# avr-atmega328p-pth.net
KiCad netlist of a schematic drawn in EAGLE
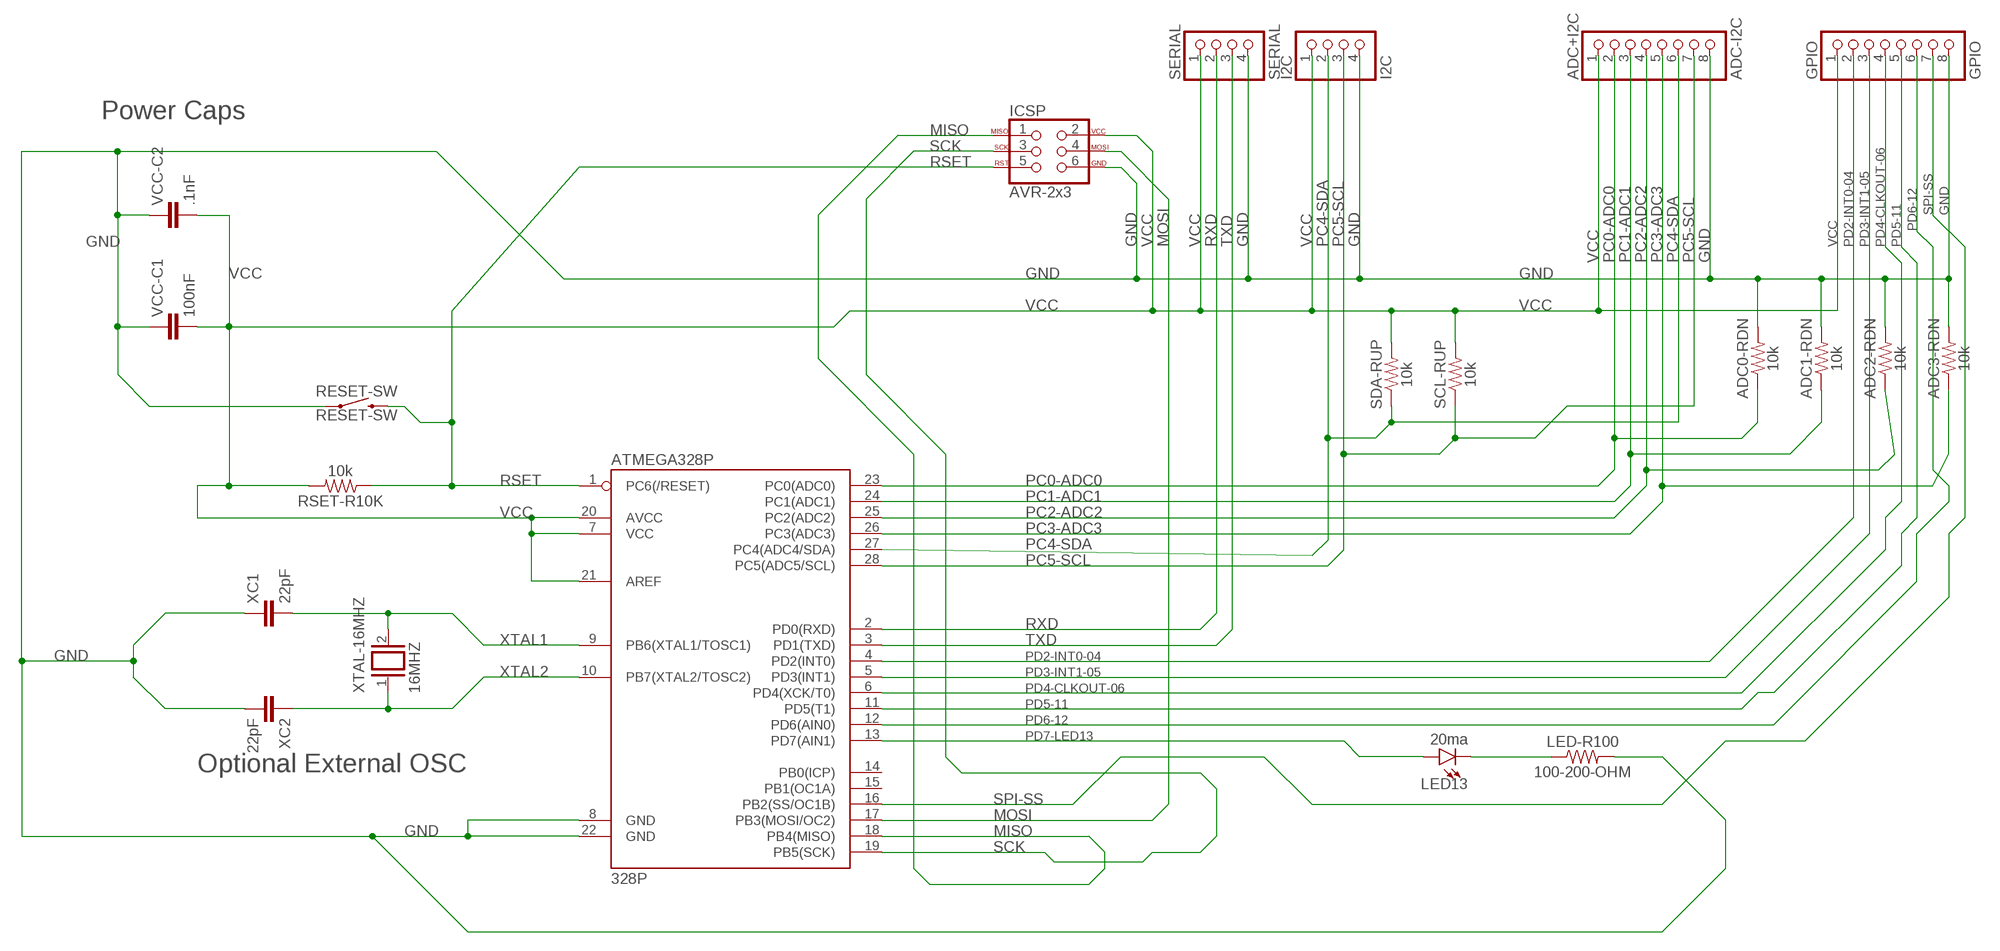
[diagram p0: schematic, sheet 1]

(export (version "E")
  (design (tool "Eeschema 10.0.6"))
  (components
    (comp (ref "ADC+I2C")
      (value "ADC-I2C")
      (footprint "eagle-import:1X08")
      (libsource (lib "eagle-import") (part "PINHD-1X8"))
    )
    (comp (ref "ADC0-RDN")
      (value "10k")
      (footprint "eagle-import:AXIAL-0.3")
      (libsource (lib "eagle-import") (part "10KOHM-HORIZ-1/4W-5%"))
    )
    (comp (ref "ADC1-RDN")
      (value "10k")
      (footprint "eagle-import:AXIAL-0.3")
      (libsource (lib "eagle-import") (part "10KOHM-HORIZ-1/4W-5%"))
    )
    (comp (ref "ADC2-RDN")
      (value "10k")
      (footprint "eagle-import:AXIAL-0.3")
      (libsource (lib "eagle-import") (part "10KOHM-HORIZ-1/4W-5%"))
    )
    (comp (ref "ADC3-RDN")
      (value "10k")
      (footprint "eagle-import:AXIAL-0.3")
      (libsource (lib "eagle-import") (part "10KOHM-HORIZ-1/4W-5%"))
    )
    (comp (ref "ATMEGA328P")
      (value "328P")
      (footprint "eagle-import:DIP28")
      (libsource (lib "eagle-import") (part "ATMEGA328P_PDIP"))
    )
    (comp (ref "GPIO")
      (value "GPIO")
      (footprint "eagle-import:1X08")
      (libsource (lib "eagle-import") (part "PINHD-1X8"))
    )
    (comp (ref "I2C")
      (value "I2C")
      (footprint "eagle-import:1X04")
      (libsource (lib "eagle-import") (part "PINHD-1X4"))
    )
    (comp (ref "ICSP")
      (value "AVR-2x3")
      (footprint "eagle-import:2X3_LOCK")
      (libsource (lib "eagle-import") (part "AVR_SPI_PROG_3X22X3_LOCK"))
    )
    (comp (ref "LED-R100")
      (value "100-200-OHM")
      (footprint "eagle-import:AXIAL-0.3")
      (libsource (lib "eagle-import") (part "10KOHM-HORIZ-1/4W-5%"))
    )
    (comp (ref "LED13")
      (value "20ma")
      (footprint "eagle-import:LED_3MM")
      (libsource (lib "eagle-import") (part "LED3MM"))
    )
    (comp (ref "RESET-SW")
      (value "RESET-SW")
      (footprint "eagle-import:TACTILE_SWITCH_PTH_6.0MM")
      (libsource (lib "eagle-import") (part "MOMENTARY-SWITCH-SPST-PTH-6.0MM"))
    )
    (comp (ref "RSET-R10K")
      (value "10k")
      (footprint "eagle-import:AXIAL-0.3")
      (libsource (lib "eagle-import") (part "10KOHM-HORIZ-1/4W-5%"))
    )
    (comp (ref "SCL-RUP")
      (value "10k")
      (footprint "eagle-import:AXIAL-0.3")
      (libsource (lib "eagle-import") (part "10KOHM-HORIZ-1/4W-5%"))
    )
    (comp (ref "SDA-RUP")
      (value "10k")
      (footprint "eagle-import:AXIAL-0.3")
      (libsource (lib "eagle-import") (part "10KOHM-HORIZ-1/4W-5%"))
    )
    (comp (ref "SERIAL")
      (value "SERIAL")
      (footprint "eagle-import:1X04")
      (libsource (lib "eagle-import") (part "PINHD-1X4"))
    )
    (comp (ref "VCC-C1")
      (value "100nF")
      (footprint "eagle-import:CAP-PTH-2.54")
      (libsource (lib "eagle-import") (part "22PF-PTH-2.54MM-200V-5%"))
    )
    (comp (ref "VCC-C2")
      (value ".1nF")
      (footprint "eagle-import:CAP-PTH-2.54")
      (libsource (lib "eagle-import") (part "22PF-PTH-2.54MM-200V-5%"))
    )
    (comp (ref "XC1")
      (value "22pF")
      (footprint "eagle-import:CAP-PTH-2.54")
      (libsource (lib "eagle-import") (part "22PF-PTH-2.54MM-200V-5%"))
    )
    (comp (ref "XC2")
      (value "22pF")
      (footprint "eagle-import:CAP-PTH-2.54")
      (libsource (lib "eagle-import") (part "22PF-PTH-2.54MM-200V-5%"))
    )
    (comp (ref "XTAL-16MHZ")
      (value "16MHZ")
      (footprint "eagle-import:QS")
      (libsource (lib "eagle-import") (part "XTAL/S"))
    )
  )
  (nets
    (net (code "1") (name "/GND") (class "Default")
      (node (ref "ADC+I2C") (pin "8") (pinfunction "8_8") (pintype "passive"))
      (node (ref "ADC0-RDN") (pin "P$2") (pinfunction "2_P$2") (pintype "passive"))
      (node (ref "ADC1-RDN") (pin "P$2") (pinfunction "2_P$2") (pintype "passive"))
      (node (ref "ADC2-RDN") (pin "P$2") (pinfunction "2_P$2") (pintype "passive"))
      (node (ref "ADC3-RDN") (pin "P$2") (pinfunction "2_P$2") (pintype "passive"))
      (node (ref "ATMEGA328P") (pin "22") (pinfunction "GND_22") (pintype "bidirectional"))
      (node (ref "ATMEGA328P") (pin "8") (pinfunction "GND_8") (pintype "bidirectional"))
      (node (ref "GPIO") (pin "8") (pinfunction "8_8") (pintype "passive"))
      (node (ref "I2C") (pin "4") (pinfunction "4_4") (pintype "passive"))
      (node (ref "ICSP") (pin "6") (pinfunction "6_6") (pintype "passive"))
      (node (ref "LED-R100") (pin "P$2") (pinfunction "2_P$2") (pintype "passive"))
      (node (ref "RESET-SW") (pin "1") (pinfunction "1_1") (pintype "passive"))
      (node (ref "SERIAL") (pin "4") (pinfunction "4_4") (pintype "passive"))
      (node (ref "VCC-C1") (pin "1") (pinfunction "1_1") (pintype "passive"))
      (node (ref "VCC-C2") (pin "1") (pinfunction "1_1") (pintype "passive"))
      (node (ref "XC1") (pin "1") (pinfunction "1_1") (pintype "passive"))
      (node (ref "XC2") (pin "2") (pinfunction "2_2") (pintype "passive"))
    )
    (net (code "2") (name "/MISO") (class "Default")
      (node (ref "ATMEGA328P") (pin "18") (pinfunction "PB4(MISO)_18") (pintype "bidirectional"))
      (node (ref "ICSP") (pin "1") (pinfunction "1_1") (pintype "passive"))
    )
    (net (code "3") (name "/MOSI") (class "Default")
      (node (ref "ATMEGA328P") (pin "17") (pinfunction "PB3(MOSI/OC2)_17") (pintype "bidirectional"))
      (node (ref "ICSP") (pin "4") (pinfunction "4_4") (pintype "passive"))
    )
    (net (code "4") (name "/PC0-ADC0") (class "Default")
      (node (ref "ADC+I2C") (pin "2") (pinfunction "2_2") (pintype "passive"))
      (node (ref "ADC0-RDN") (pin "P$1") (pinfunction "1_P$1") (pintype "passive"))
      (node (ref "ATMEGA328P") (pin "23") (pinfunction "PC0(ADC0)_23") (pintype "bidirectional"))
    )
    (net (code "5") (name "/PC1-ADC1") (class "Default")
      (node (ref "ADC+I2C") (pin "3") (pinfunction "3_3") (pintype "passive"))
      (node (ref "ADC1-RDN") (pin "P$1") (pinfunction "1_P$1") (pintype "passive"))
      (node (ref "ATMEGA328P") (pin "24") (pinfunction "PC1(ADC1)_24") (pintype "bidirectional"))
    )
    (net (code "6") (name "/PC2-ADC2") (class "Default")
      (node (ref "ADC+I2C") (pin "4") (pinfunction "4_4") (pintype "passive"))
      (node (ref "ADC2-RDN") (pin "P$1") (pinfunction "1_P$1") (pintype "passive"))
      (node (ref "ATMEGA328P") (pin "25") (pinfunction "PC2(ADC2)_25") (pintype "bidirectional"))
    )
    (net (code "7") (name "/PC3-ADC3") (class "Default")
      (node (ref "ADC+I2C") (pin "5") (pinfunction "5_5") (pintype "passive"))
      (node (ref "ADC3-RDN") (pin "P$1") (pinfunction "1_P$1") (pintype "passive"))
      (node (ref "ATMEGA328P") (pin "26") (pinfunction "PC3(ADC3)_26") (pintype "bidirectional"))
    )
    (net (code "8") (name "/PC4-SDA") (class "Default")
      (node (ref "ADC+I2C") (pin "6") (pinfunction "6_6") (pintype "passive"))
      (node (ref "ATMEGA328P") (pin "27") (pinfunction "PC4(ADC4/SDA)_27") (pintype "bidirectional"))
      (node (ref "I2C") (pin "2") (pinfunction "2_2") (pintype "passive"))
      (node (ref "SDA-RUP") (pin "P$1") (pinfunction "1_P$1") (pintype "passive"))
    )
    (net (code "9") (name "/PC5-SCL") (class "Default")
      (node (ref "ADC+I2C") (pin "7") (pinfunction "7_7") (pintype "passive"))
      (node (ref "ATMEGA328P") (pin "28") (pinfunction "PC5(ADC5/SCL)_28") (pintype "bidirectional"))
      (node (ref "I2C") (pin "3") (pinfunction "3_3") (pintype "passive"))
      (node (ref "SCL-RUP") (pin "P$1") (pinfunction "1_P$1") (pintype "passive"))
    )
    (net (code "10") (name "/PD2-INT0-04") (class "Default")
      (node (ref "ATMEGA328P") (pin "4") (pinfunction "PD2(INT0)_4") (pintype "bidirectional"))
      (node (ref "GPIO") (pin "2") (pinfunction "2_2") (pintype "passive"))
    )
    (net (code "11") (name "/PD3-INT1-05") (class "Default")
      (node (ref "ATMEGA328P") (pin "5") (pinfunction "PD3(INT1)_5") (pintype "bidirectional"))
      (node (ref "GPIO") (pin "3") (pinfunction "3_3") (pintype "passive"))
    )
    (net (code "12") (name "/PD4-CLKOUT-06") (class "Default")
      (node (ref "ATMEGA328P") (pin "6") (pinfunction "PD4(XCK/T0)_6") (pintype "bidirectional"))
      (node (ref "GPIO") (pin "4") (pinfunction "4_4") (pintype "passive"))
    )
    (net (code "13") (name "/PD5-11") (class "Default")
      (node (ref "ATMEGA328P") (pin "11") (pinfunction "PD5(T1)_11") (pintype "bidirectional"))
      (node (ref "GPIO") (pin "5") (pinfunction "5_5") (pintype "passive"))
    )
    (net (code "14") (name "/PD6-12") (class "Default")
      (node (ref "ATMEGA328P") (pin "12") (pinfunction "PD6(AIN0)_12") (pintype "bidirectional"))
      (node (ref "GPIO") (pin "6") (pinfunction "6_6") (pintype "passive"))
    )
    (net (code "15") (name "/PD7-LED13") (class "Default")
      (node (ref "ATMEGA328P") (pin "13") (pinfunction "PD7(AIN1)_13") (pintype "bidirectional"))
      (node (ref "LED13") (pin "A") (pinfunction "A_A") (pintype "passive"))
    )
    (net (code "16") (name "/RSET") (class "Default")
      (node (ref "ATMEGA328P") (pin "1") (pinfunction "PC6(/RESET)_1") (pintype "bidirectional"))
      (node (ref "ICSP") (pin "5") (pinfunction "5_5") (pintype "passive"))
      (node (ref "RESET-SW") (pin "3") (pinfunction "2_3") (pintype "passive"))
      (node (ref "RSET-R10K") (pin "P$1") (pinfunction "1_P$1") (pintype "passive"))
    )
    (net (code "17") (name "/RXD") (class "Default")
      (node (ref "ATMEGA328P") (pin "2") (pinfunction "PD0(RXD)_2") (pintype "bidirectional"))
      (node (ref "SERIAL") (pin "2") (pinfunction "2_2") (pintype "passive"))
    )
    (net (code "18") (name "/SCK") (class "Default")
      (node (ref "ATMEGA328P") (pin "19") (pinfunction "PB5(SCK)_19") (pintype "bidirectional"))
      (node (ref "ICSP") (pin "3") (pinfunction "3_3") (pintype "passive"))
    )
    (net (code "19") (name "/SPI-SS") (class "Default")
      (node (ref "ATMEGA328P") (pin "16") (pinfunction "PB2(SS/OC1B)_16") (pintype "bidirectional"))
      (node (ref "GPIO") (pin "7") (pinfunction "7_7") (pintype "passive"))
    )
    (net (code "20") (name "/TXD") (class "Default")
      (node (ref "ATMEGA328P") (pin "3") (pinfunction "PD1(TXD)_3") (pintype "bidirectional"))
      (node (ref "SERIAL") (pin "3") (pinfunction "3_3") (pintype "passive"))
    )
    (net (code "21") (name "/VCC") (class "Default")
      (node (ref "ADC+I2C") (pin "1") (pinfunction "1_1") (pintype "passive"))
      (node (ref "ATMEGA328P") (pin "20") (pinfunction "AVCC_20") (pintype "bidirectional"))
      (node (ref "ATMEGA328P") (pin "21") (pinfunction "AREF_21") (pintype "bidirectional"))
      (node (ref "ATMEGA328P") (pin "7") (pinfunction "VCC_7") (pintype "bidirectional"))
      (node (ref "GPIO") (pin "1") (pinfunction "1_1") (pintype "passive"))
      (node (ref "I2C") (pin "1") (pinfunction "1_1") (pintype "passive"))
      (node (ref "ICSP") (pin "2") (pinfunction "2_2") (pintype "passive"))
      (node (ref "RSET-R10K") (pin "P$2") (pinfunction "2_P$2") (pintype "passive"))
      (node (ref "SCL-RUP") (pin "P$2") (pinfunction "2_P$2") (pintype "passive"))
      (node (ref "SDA-RUP") (pin "P$2") (pinfunction "2_P$2") (pintype "passive"))
      (node (ref "SERIAL") (pin "1") (pinfunction "1_1") (pintype "passive"))
      (node (ref "VCC-C1") (pin "2") (pinfunction "2_2") (pintype "passive"))
      (node (ref "VCC-C2") (pin "2") (pinfunction "2_2") (pintype "passive"))
    )
    (net (code "22") (name "/XTAL1") (class "Default")
      (node (ref "ATMEGA328P") (pin "9") (pinfunction "PB6(XTAL1/TOSC1)_9") (pintype "bidirectional"))
      (node (ref "XC1") (pin "2") (pinfunction "2_2") (pintype "passive"))
      (node (ref "XTAL-16MHZ") (pin "2") (pinfunction "2_2") (pintype "passive"))
    )
    (net (code "23") (name "/XTAL2") (class "Default")
      (node (ref "ATMEGA328P") (pin "10") (pinfunction "PB7(XTAL2/TOSC2)_10") (pintype "bidirectional"))
      (node (ref "XC2") (pin "1") (pinfunction "1_1") (pintype "passive"))
      (node (ref "XTAL-16MHZ") (pin "1") (pinfunction "1_1") (pintype "passive"))
    )
    (net (code "24") (name "Net-(LED-R100-1)") (class "Default")
      (node (ref "LED-R100") (pin "P$1") (pinfunction "1_P$1") (pintype "passive"))
      (node (ref "LED13") (pin "K") (pinfunction "C_K") (pintype "passive"))
    )
    (net (code "25") (name "unconnected-(ATMEGA328P-PB0(ICP)-Pad14)") (class "Default")
      (node (ref "ATMEGA328P") (pin "14") (pinfunction "PB0(ICP)_14") (pintype "bidirectional"))
    )
    (net (code "26") (name "unconnected-(ATMEGA328P-PB1(OC1A)-Pad15)") (class "Default")
      (node (ref "ATMEGA328P") (pin "15") (pinfunction "PB1(OC1A)_15") (pintype "bidirectional"))
    )
  )
)
